# LM74910H_PINOUT.net
KiCad netlist of a schematic drawn in Altium Designer
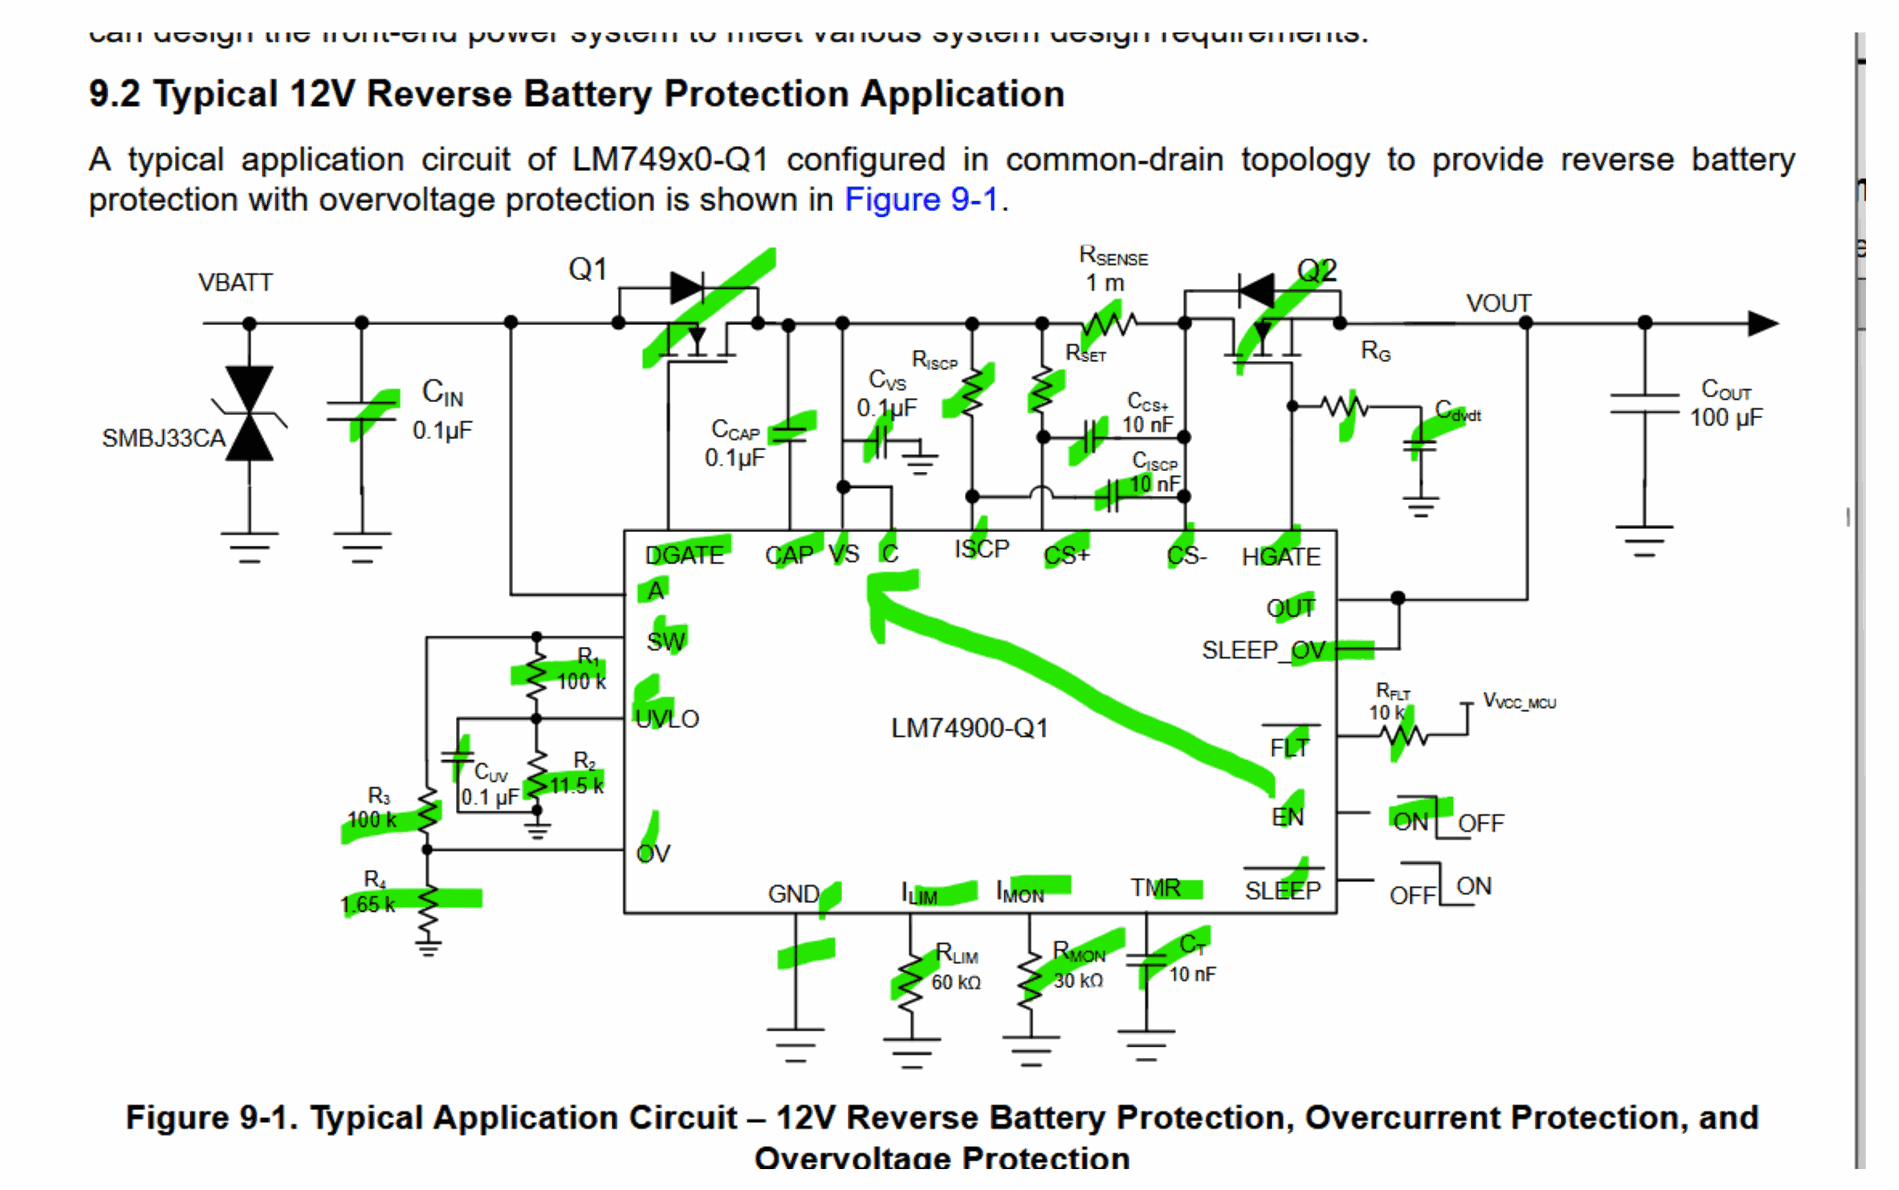
[diagram p0: LM74910H_PINOUT.SchDoc, top]
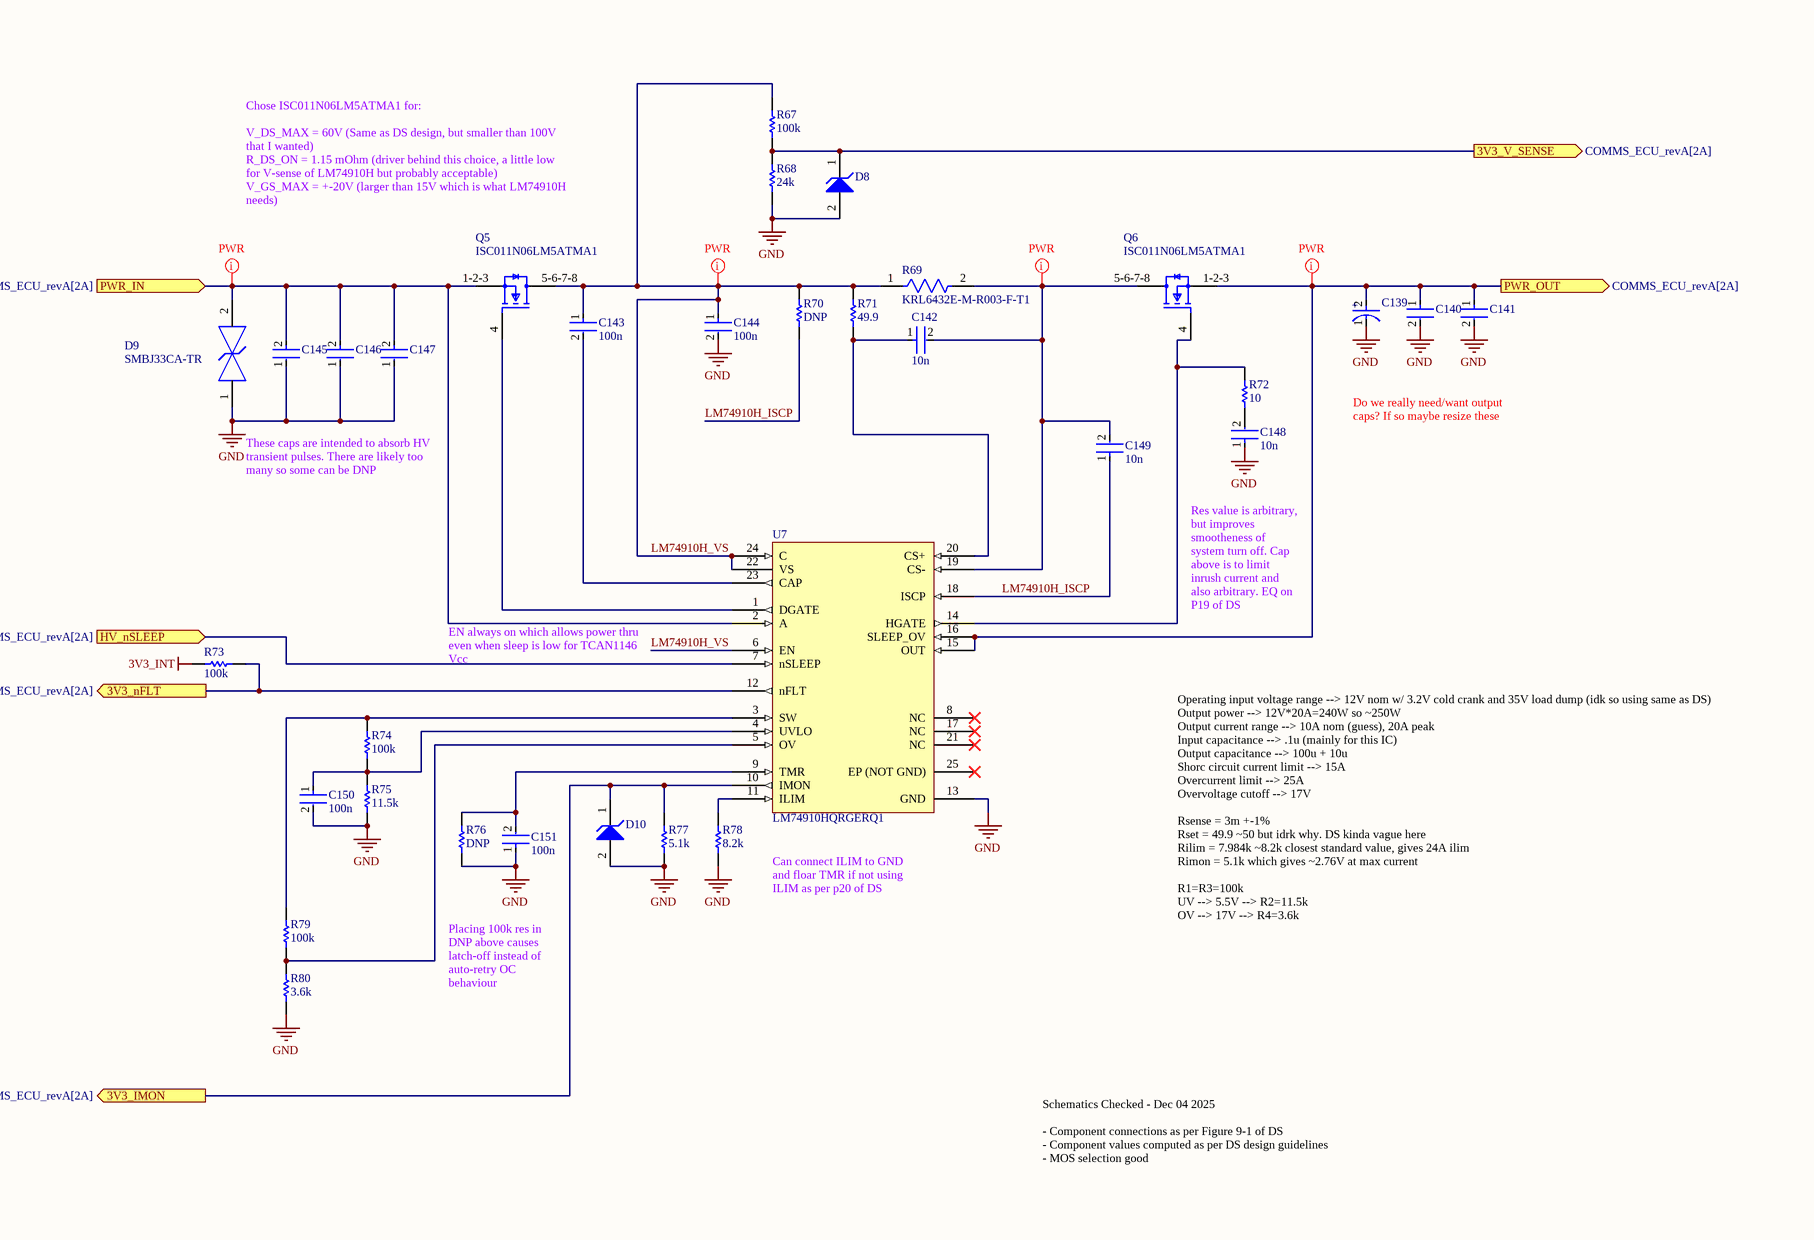
[diagram p1: LM74910H_PINOUT.SchDoc, bottom]

(export (version "E")
  (design (tool "Eeschema 10.0.6"))
  (components
    (comp (ref "C139")
      (value "EEE-FK1H100UR")
      (footprint "FP-FKC-MFG")
      (description "CAP ALUM 10UF 20% 50V SMD")
      (fields (field (name "TOLERANCE") "20%") (field (name "VOLTAGE") "50V"))
      (libsource (lib "Altium Content Vault") (part "a00bbbee19879c290e62620ae7e47b1"))
    )
    (comp (ref "C140")
      (value "12103D106KAT2A")
      (footprint "FP-1210-L_3_3_0_4-W_2_5_0-MFG")
      (description "General Purpose Ceramic Capacitor, 1210, 10uF, 10%, X5R, 15%, 25V")
      (fields (field (name "VOLTAGE") "25V") (field (name "TOLERANCE") "10%"))
      (libsource (lib "Altium Content Vault") (part "b4654b650e69147ec39a6b967a45e02"))
    )
    (comp (ref "C141")
      (value "12103D106KAT2A")
      (footprint "FP-1210-L_3_3_0_4-W_2_5_0-MFG")
      (description "General Purpose Ceramic Capacitor, 1210, 10uF, 10%, X5R, 15%, 25V")
      (fields (field (name "VOLTAGE") "25V") (field (name "TOLERANCE") "10%"))
      (libsource (lib "Altium Content Vault") (part "b4654b650e69147ec39a6b967a45e02"))
    )
    (comp (ref "C142")
      (value "10n")
      (footprint "FP-0402-L_1_0_0_05-W_0_5-IPC_A")
      (description "LARGE PADS, 0402 CAP, CHANGE COMMENT TO MATCH REAL P/N")
      (libsource (lib "Space Concordia") (part "b4654b650e69147ec39a6b967a45e02"))
    )
    (comp (ref "C143")
      (value "100n")
      (footprint "FP-0402-L_1_0_0_05-W_0_5-IPC_A")
      (description "LARGE PADS, 0402 CAP, CHANGE COMMENT TO MATCH REAL P/N")
      (libsource (lib "Space Concordia") (part "b4654b650e69147ec39a6b967a45e02"))
    )
    (comp (ref "C144")
      (value "100n")
      (footprint "FP-0402-L_1_0_0_05-W_0_5-IPC_A")
      (description "LARGE PADS, 0402 CAP, CHANGE COMMENT TO MATCH REAL P/N")
      (libsource (lib "Space Concordia") (part "b4654b650e69147ec39a6b967a45e02"))
    )
    (comp (ref "C145")
      (value "AC1210KKX7R0BB104")
      (footprint "FP-AC1210-0_85-MFG")
      (description "CAP CER 0.1UF 100V X7R 1210")
      (fields (field (name "MANUFACTURER") "Yageo") (field (name "TOLERANCE") "0.1"))
      (libsource (lib "Altium Content Vault") (part "236180d848d6139a670b325ea6854c9"))
    )
    (comp (ref "C146")
      (value "AC1210KKX7R0BB104")
      (footprint "FP-AC1210-0_85-MFG")
      (description "CAP CER 0.1UF 100V X7R 1210")
      (fields (field (name "MANUFACTURER") "Yageo") (field (name "TOLERANCE") "0.1"))
      (libsource (lib "Altium Content Vault") (part "236180d848d6139a670b325ea6854c9"))
    )
    (comp (ref "C147")
      (value "AC1210KKX7R0BB104")
      (footprint "FP-AC1210-0_85-MFG")
      (description "CAP CER 0.1UF 100V X7R 1210")
      (fields (field (name "MANUFACTURER") "Yageo") (field (name "TOLERANCE") "0.1"))
      (libsource (lib "Altium Content Vault") (part "236180d848d6139a670b325ea6854c9"))
    )
    (comp (ref "C148")
      (value "10n")
      (footprint "FP-0402-L_1_0_0_05-W_0_5-IPC_A")
      (description "LARGE PADS, 0402 CAP, CHANGE COMMENT TO MATCH REAL P/N")
      (libsource (lib "Space Concordia") (part "b4654b650e69147ec39a6b967a45e02"))
    )
    (comp (ref "C149")
      (value "10n")
      (footprint "FP-0402-L_1_0_0_05-W_0_5-IPC_A")
      (description "LARGE PADS, 0402 CAP, CHANGE COMMENT TO MATCH REAL P/N")
      (libsource (lib "Space Concordia") (part "b4654b650e69147ec39a6b967a45e02"))
    )
    (comp (ref "C150")
      (value "100n")
      (footprint "FP-0402-L_1_0_0_05-W_0_5-IPC_A")
      (description "LARGE PADS, 0402 CAP, CHANGE COMMENT TO MATCH REAL P/N")
      (libsource (lib "Space Concordia") (part "b4654b650e69147ec39a6b967a45e02"))
    )
    (comp (ref "C151")
      (value "100n")
      (footprint "FP-0402-L_1_0_0_05-W_0_5-IPC_A")
      (description "LARGE PADS, 0402 CAP, CHANGE COMMENT TO MATCH REAL P/N")
      (libsource (lib "Space Concordia") (part "b4654b650e69147ec39a6b967a45e02"))
    )
    (comp (ref "D8")
      (value "DNP/MM5Z3V3T1G")
      (footprint "ONSC-SOD-523-2-502-01_V")
      (description "Zener Voltage Regulator, 500 mW, 2-Pin SOD-523, Pb-Free, Tape and Reel")
      (fields (field (name "MANUFACTURER") "On Semiconductor") (field (name "PARTNUMBER") "MM5Z3V3T1G"))
      (libsource (lib "Altium Content Vault") (part "ONSC-K1A2-2"))
    )
    (comp (ref "D9")
      (value "SMBJ33CA-TR")
      (footprint "FP-SMB-CA-MFG")
      (description "TVS DIODE 33V 69.7V SMB")
      (fields
        (field (name "OCTOPART") "https://octopart.com/smbj33ca-tr-stmicroelectronics-347069")
        (field (name "MANUFACTURER") "STMicroelectronics")
      )
      (libsource (lib "Altium Content Vault") (part "11bd9d59d340f0612179daf16ad9b72"))
    )
    (comp (ref "D10")
      (value "DNP/MM5Z3V3T1G")
      (footprint "ONSC-SOD-523-2-502-01_V")
      (description "Zener Voltage Regulator, 500 mW, 2-Pin SOD-523, Pb-Free, Tape and Reel")
      (fields (field (name "MANUFACTURER") "On Semiconductor") (field (name "PARTNUMBER") "MM5Z3V3T1G"))
      (libsource (lib "Altium Content Vault") (part "ONSC-K1A2-2"))
    )
    (comp (ref "Q5")
      (value "ISC011N06LM5ATMA1")
      (footprint "FP-PG-TDSON-8-MFG")
      (description "TRENCH 40<-<100V PG-TDSON-8")
      (libsource (lib "Altium Content Vault") (part "3085234d4498bcd04bc7e5400bb7c96"))
    )
    (comp (ref "Q6")
      (value "ISC011N06LM5ATMA1")
      (footprint "FP-PG-TDSON-8-MFG")
      (description "TRENCH 40<-<100V PG-TDSON-8")
      (libsource (lib "Altium Content Vault") (part "3085234d4498bcd04bc7e5400bb7c96"))
    )
    (comp (ref "R67")
      (value "100k")
      (footprint "R0603B")
      (description "Resistor")
      (libsource (lib "Space Concordia") (part "Resistor"))
    )
    (comp (ref "R68")
      (value "24k")
      (footprint "R0603B")
      (description "Resistor")
      (libsource (lib "Space Concordia") (part "Resistor"))
    )
    (comp (ref "R69")
      (value "KRL6432E-M-R003-F-T1")
      (footprint "FP-KRL6432E-MFG")
      (description "KRL6432E-M-R003-F-T1 Metal Foil Low Resistance Chip Resistor (long-side terminal), 2512, RoHS")
      (fields (field (name "TOLERANCE") "1%"))
      (libsource (lib "Altium Content Vault") (part "1029c3af85768c4190bb7ad29bc67b5"))
    )
    (comp (ref "R70")
      (value "DNP")
      (footprint "R0603B")
      (description "Resistor")
      (libsource (lib "Space Concordia") (part "Resistor"))
    )
    (comp (ref "R71")
      (value "49.9")
      (footprint "R0603B")
      (description "Resistor")
      (libsource (lib "Space Concordia") (part "Resistor"))
    )
    (comp (ref "R72")
      (value "10")
      (footprint "R0603B")
      (description "Resistor")
      (libsource (lib "Space Concordia") (part "Resistor"))
    )
    (comp (ref "R73")
      (value "100k")
      (footprint "R0603B")
      (description "Resistor")
      (libsource (lib "Space Concordia") (part "Resistor"))
    )
    (comp (ref "R74")
      (value "100k")
      (footprint "R0603B")
      (description "Resistor")
      (libsource (lib "Space Concordia") (part "Resistor"))
    )
    (comp (ref "R75")
      (value "11.5k")
      (footprint "R0603B")
      (description "Resistor")
      (libsource (lib "Space Concordia") (part "Resistor"))
    )
    (comp (ref "R76")
      (value "DNP")
      (footprint "R0603B")
      (description "Resistor")
      (libsource (lib "Space Concordia") (part "Resistor"))
    )
    (comp (ref "R77")
      (value "5.1k")
      (footprint "R0603B")
      (description "Resistor")
      (libsource (lib "Space Concordia") (part "Resistor"))
    )
    (comp (ref "R78")
      (value "8.2k")
      (footprint "R0603B")
      (description "Resistor")
      (libsource (lib "Space Concordia") (part "Resistor"))
    )
    (comp (ref "R79")
      (value "100k")
      (footprint "R0603B")
      (description "Resistor")
      (libsource (lib "Space Concordia") (part "Resistor"))
    )
    (comp (ref "R80")
      (value "3.6k")
      (footprint "R0603B")
      (description "Resistor")
      (libsource (lib "Space Concordia") (part "Resistor"))
    )
    (comp (ref "U7")
      (value "LM74910HQRGERQ1")
      (footprint "QFN50P400X400X100_HS-25N")
      (libsource (lib "Space Concordia") (part "LM74910HQRGERQ1"))
    )
  )
  (nets
    (net (code "1") (name "/3V3_IMON") (class "Default")
      (node (ref "D10") (pin "1") (pinfunction "K_1") (pintype "passive"))
      (node (ref "R77") (pin "2") (pinfunction "2_2") (pintype "passive"))
      (node (ref "U7") (pin "10") (pinfunction "IMON_10") (pintype "output"))
    )
    (net (code "2") (name "/3V3_V_SENSE") (class "Default")
      (node (ref "D8") (pin "1") (pinfunction "K_1") (pintype "passive"))
      (node (ref "R67") (pin "1") (pinfunction "1_1") (pintype "passive"))
      (node (ref "R68") (pin "2") (pinfunction "2_2") (pintype "passive"))
    )
    (net (code "3") (name "/3V3_nFLT") (class "Default")
      (node (ref "R73") (pin "1") (pinfunction "1_1") (pintype "passive"))
      (node (ref "U7") (pin "12") (pinfunction "nFLT_12") (pintype "output"))
    )
    (net (code "4") (name "/HV_nSLEEP") (class "Default")
      (node (ref "U7") (pin "7") (pinfunction "nSLEEP_7") (pintype "input"))
    )
    (net (code "5") (name "/LM74910H_ISCP") (class "Default")
      (node (ref "C149") (pin "1") (pinfunction "1_1") (pintype "passive"))
      (node (ref "R70") (pin "1") (pinfunction "1_1") (pintype "passive"))
      (node (ref "U7") (pin "18") (pinfunction "ISCP_18") (pintype "input"))
    )
    (net (code "6") (name "/LM74910H_VS") (class "Default")
      (node (ref "C143") (pin "1") (pinfunction "1_1") (pintype "passive"))
      (node (ref "C144") (pin "1") (pinfunction "1_1") (pintype "passive"))
      (node (ref "Q5") (pin "5-6-7-8") (pinfunction "D_5-6-7-8") (pintype "passive"))
      (node (ref "R67") (pin "2") (pinfunction "2_2") (pintype "passive"))
      (node (ref "R69") (pin "1") (pinfunction "1_1") (pintype "passive"))
      (node (ref "R70") (pin "2") (pinfunction "2_2") (pintype "passive"))
      (node (ref "R71") (pin "2") (pinfunction "2_2") (pintype "passive"))
      (node (ref "U7") (pin "22") (pinfunction "VS_22") (pintype "power_in"))
      (node (ref "U7") (pin "24") (pinfunction "C_24") (pintype "input"))
      (node (ref "U7") (pin "6") (pinfunction "EN_6") (pintype "input"))
    )
    (net (code "7") (name "/PWR_IN") (class "Default")
      (node (ref "C145") (pin "2") (pinfunction "2_2") (pintype "passive"))
      (node (ref "C146") (pin "2") (pinfunction "2_2") (pintype "passive"))
      (node (ref "C147") (pin "2") (pinfunction "2_2") (pintype "passive"))
      (node (ref "D9") (pin "2") (pinfunction "2_2") (pintype "passive"))
      (node (ref "Q5") (pin "1-2-3") (pinfunction "S_1-2-3") (pintype "passive"))
      (node (ref "U7") (pin "2") (pinfunction "A_2") (pintype "input"))
    )
    (net (code "8") (name "/PWR_OUT") (class "Default")
      (node (ref "C139") (pin "2") (pinfunction "A_2") (pintype "passive"))
      (node (ref "C140") (pin "1") (pinfunction "1_1") (pintype "passive"))
      (node (ref "C141") (pin "1") (pinfunction "1_1") (pintype "passive"))
      (node (ref "Q6") (pin "1-2-3") (pinfunction "S_1-2-3") (pintype "passive"))
      (node (ref "U7") (pin "15") (pinfunction "OUT_15") (pintype "input"))
      (node (ref "U7") (pin "16") (pinfunction "SLEEP_OV_16") (pintype "input"))
    )
    (net (code "9") (name "3V3_INT") (class "Default")
      (node (ref "R73") (pin "2") (pinfunction "2_2") (pintype "passive"))
    )
    (net (code "10") (name "GND") (class "Default")
      (node (ref "C139") (pin "1") (pinfunction "C_1") (pintype "passive"))
      (node (ref "C140") (pin "2") (pinfunction "2_2") (pintype "passive"))
      (node (ref "C141") (pin "2") (pinfunction "2_2") (pintype "passive"))
      (node (ref "C144") (pin "2") (pinfunction "2_2") (pintype "passive"))
      (node (ref "C145") (pin "1") (pinfunction "1_1") (pintype "passive"))
      (node (ref "C146") (pin "1") (pinfunction "1_1") (pintype "passive"))
      (node (ref "C147") (pin "1") (pinfunction "1_1") (pintype "passive"))
      (node (ref "C148") (pin "1") (pinfunction "1_1") (pintype "passive"))
      (node (ref "C150") (pin "2") (pinfunction "2_2") (pintype "passive"))
      (node (ref "C151") (pin "1") (pinfunction "1_1") (pintype "passive"))
      (node (ref "D10") (pin "2") (pinfunction "A_2") (pintype "passive"))
      (node (ref "D8") (pin "2") (pinfunction "A_2") (pintype "passive"))
      (node (ref "D9") (pin "1") (pinfunction "1_1") (pintype "passive"))
      (node (ref "R68") (pin "1") (pinfunction "1_1") (pintype "passive"))
      (node (ref "R75") (pin "1") (pinfunction "1_1") (pintype "passive"))
      (node (ref "R76") (pin "1") (pinfunction "1_1") (pintype "passive"))
      (node (ref "R77") (pin "1") (pinfunction "1_1") (pintype "passive"))
      (node (ref "R78") (pin "1") (pinfunction "1_1") (pintype "passive"))
      (node (ref "R80") (pin "1") (pinfunction "1_1") (pintype "passive"))
      (node (ref "U7") (pin "13") (pinfunction "GND_13") (pintype "power_in"))
    )
    (net (code "11") (name "Net-(C148-Pad2)") (class "Default")
      (node (ref "C148") (pin "2") (pinfunction "2_2") (pintype "passive"))
      (node (ref "R72") (pin "1") (pinfunction "1_1") (pintype "passive"))
    )
    (net (code "12") (name "Net-(Q5-G)") (class "Default")
      (node (ref "Q5") (pin "4") (pinfunction "G_4") (pintype "passive"))
      (node (ref "U7") (pin "1") (pinfunction "DGATE_1") (pintype "output"))
    )
    (net (code "13") (name "Net-(Q6-D)") (class "Default")
      (node (ref "C142") (pin "2") (pinfunction "2_2") (pintype "passive"))
      (node (ref "C149") (pin "2") (pinfunction "2_2") (pintype "passive"))
      (node (ref "Q6") (pin "5-6-7-8") (pinfunction "D_5-6-7-8") (pintype "passive"))
      (node (ref "R69") (pin "2") (pinfunction "2_2") (pintype "passive"))
      (node (ref "U7") (pin "19") (pinfunction "CS-_19") (pintype "input"))
    )
    (net (code "14") (name "Net-(Q6-G)") (class "Default")
      (node (ref "Q6") (pin "4") (pinfunction "G_4") (pintype "passive"))
      (node (ref "R72") (pin "2") (pinfunction "2_2") (pintype "passive"))
      (node (ref "U7") (pin "14") (pinfunction "HGATE_14") (pintype "output"))
    )
    (net (code "15") (name "Net-(U7-CAP)") (class "Default")
      (node (ref "C143") (pin "2") (pinfunction "2_2") (pintype "passive"))
      (node (ref "U7") (pin "23") (pinfunction "CAP_23") (pintype "output"))
    )
    (net (code "16") (name "Net-(U7-CS+)") (class "Default")
      (node (ref "C142") (pin "1") (pinfunction "1_1") (pintype "passive"))
      (node (ref "R71") (pin "1") (pinfunction "1_1") (pintype "passive"))
      (node (ref "U7") (pin "20") (pinfunction "CS+_20") (pintype "input"))
    )
    (net (code "17") (name "Net-(U7-ILIM)") (class "Default")
      (node (ref "R78") (pin "2") (pinfunction "2_2") (pintype "passive"))
      (node (ref "U7") (pin "11") (pinfunction "ILIM_11") (pintype "input"))
    )
    (net (code "18") (name "Net-(U7-OV)") (class "Default")
      (node (ref "R79") (pin "1") (pinfunction "1_1") (pintype "passive"))
      (node (ref "R80") (pin "2") (pinfunction "2_2") (pintype "passive"))
      (node (ref "U7") (pin "5") (pinfunction "OV_5") (pintype "input"))
    )
    (net (code "19") (name "Net-(U7-SW)") (class "Default")
      (node (ref "R74") (pin "2") (pinfunction "2_2") (pintype "passive"))
      (node (ref "R79") (pin "2") (pinfunction "2_2") (pintype "passive"))
      (node (ref "U7") (pin "3") (pinfunction "SW_3") (pintype "input"))
    )
    (net (code "20") (name "Net-(U7-TMR)") (class "Default")
      (node (ref "C151") (pin "2") (pinfunction "2_2") (pintype "passive"))
      (node (ref "R76") (pin "2") (pinfunction "2_2") (pintype "passive"))
      (node (ref "U7") (pin "9") (pinfunction "TMR_9") (pintype "input"))
    )
    (net (code "21") (name "Net-(U7-UVLO)") (class "Default")
      (node (ref "C150") (pin "1") (pinfunction "1_1") (pintype "passive"))
      (node (ref "R74") (pin "1") (pinfunction "1_1") (pintype "passive"))
      (node (ref "R75") (pin "2") (pinfunction "2_2") (pintype "passive"))
      (node (ref "U7") (pin "4") (pinfunction "UVLO_4") (pintype "input"))
    )
    (net (code "22") (name "unconnected-(U7-EP_(NOT_GND)-Pad25)") (class "Default")
      (node (ref "U7") (pin "25") (pinfunction "EP_(NOT_GND)_25") (pintype "passive+no_connect"))
    )
    (net (code "23") (name "unconnected-(U7-NC-Pad8)") (class "Default")
      (node (ref "U7") (pin "8") (pinfunction "NC_8") (pintype "passive+no_connect"))
    )
    (net (code "24") (name "unconnected-(U7-NC-Pad17)") (class "Default")
      (node (ref "U7") (pin "17") (pinfunction "NC_17") (pintype "passive+no_connect"))
    )
    (net (code "25") (name "unconnected-(U7-NC-Pad21)") (class "Default")
      (node (ref "U7") (pin "21") (pinfunction "NC_21") (pintype "passive+no_connect"))
    )
  )
)
